# 7V4_2.net
KiCad netlist of a schematic drawn in Altium Designer
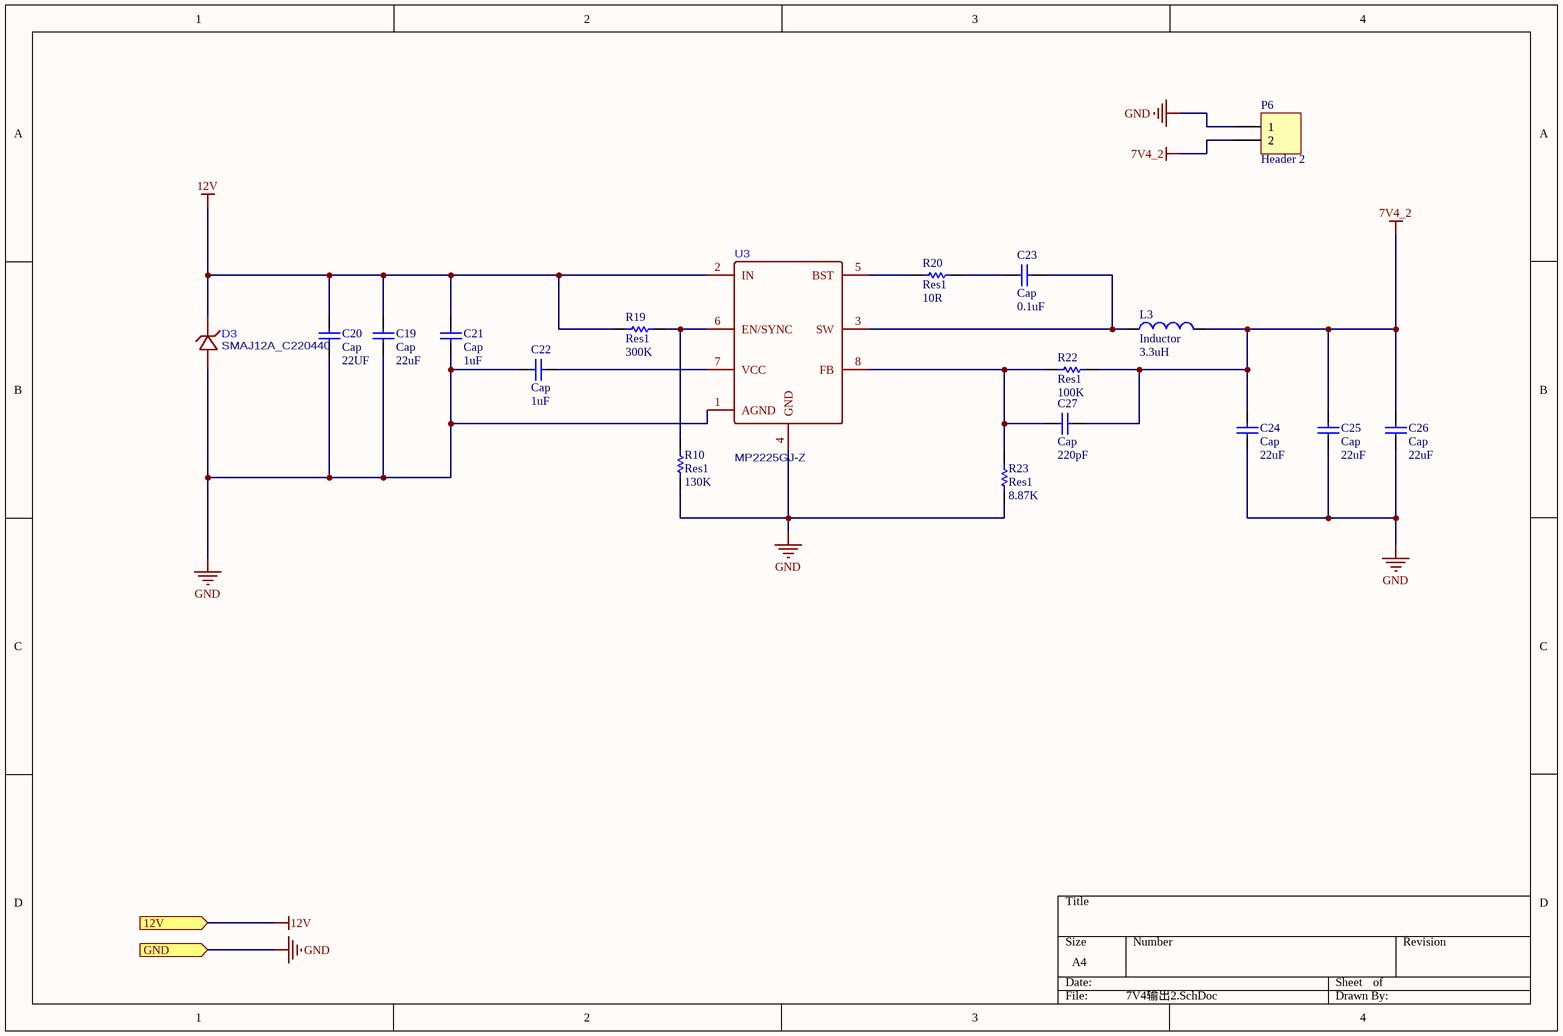
[diagram p0: 7V4输出2.SchDoc]

(export (version "E")
  (design (tool "Eeschema 10.0.6"))
  (components
    (comp (ref "C19")
      (value "Cap")
      (footprint "C1206")
      (description "Capacitor")
      (fields (field (name "ALTIUM_VALUE") "22uF") (field (name "PUBLISHER") "Altium Limited"))
      (libsource (lib "Miscellaneous Devices") (part "Cap"))
    )
    (comp (ref "C20")
      (value "Cap")
      (footprint "C1206")
      (description "Capacitor")
      (fields (field (name "ALTIUM_VALUE") "22UF") (field (name "PUBLISHER") "Altium Limited"))
      (libsource (lib "Miscellaneous Devices") (part "Cap"))
    )
    (comp (ref "C21")
      (value "Cap")
      (footprint "R0603")
      (description "Capacitor")
      (fields (field (name "ALTIUM_VALUE") "1uF") (field (name "PUBLISHER") "Altium Limited"))
      (libsource (lib "Miscellaneous Devices") (part "Cap"))
    )
    (comp (ref "C22")
      (value "Cap")
      (footprint "R0603")
      (description "Capacitor")
      (fields (field (name "ALTIUM_VALUE") "1uF") (field (name "PUBLISHER") "Altium Limited"))
      (libsource (lib "Miscellaneous Devices") (part "Cap"))
    )
    (comp (ref "C23")
      (value "Cap")
      (footprint "R0603")
      (description "Capacitor")
      (fields (field (name "ALTIUM_VALUE") "0.1uF") (field (name "PUBLISHER") "Altium Limited"))
      (libsource (lib "Miscellaneous Devices") (part "Cap"))
    )
    (comp (ref "C24")
      (value "Cap")
      (footprint "C0805")
      (description "Capacitor")
      (fields (field (name "ALTIUM_VALUE") "22uF") (field (name "PUBLISHER") "Altium Limited"))
      (libsource (lib "Miscellaneous Devices") (part "Cap"))
    )
    (comp (ref "C25")
      (value "Cap")
      (footprint "C0805")
      (description "Capacitor")
      (fields (field (name "ALTIUM_VALUE") "22uF") (field (name "PUBLISHER") "Altium Limited"))
      (libsource (lib "Miscellaneous Devices") (part "Cap"))
    )
    (comp (ref "C26")
      (value "Cap")
      (footprint "C0805")
      (description "Capacitor")
      (fields (field (name "ALTIUM_VALUE") "22uF") (field (name "PUBLISHER") "Altium Limited"))
      (libsource (lib "Miscellaneous Devices") (part "Cap"))
    )
    (comp (ref "C27")
      (value "Cap")
      (footprint "R0603")
      (description "Capacitor")
      (fields (field (name "ALTIUM_VALUE") "220pF") (field (name "PUBLISHER") "Altium Limited"))
      (libsource (lib "Miscellaneous Devices") (part "Cap"))
    )
    (comp (ref "D3")
      (value "SMAJ12A_C220440")
      (footprint "SMA_L4.4-W2.8-LS5.4-RD")
      (libsource (lib "SMAJ12A_C220440_2021-10-18") (part "SMAJ12A_C220440"))
    )
    (comp (ref "L3")
      (value "Inductor")
      (footprint "IND-SMD_L7.8-W7.0_MAPM0630F")
      (fields (field (name "ALTIUM_VALUE") "3.3uH") (field (name "PUBLISHER") "Altium Limited"))
      (libsource (lib "Miscellaneous Devices") (part "Inductor"))
    )
    (comp (ref "P6")
      (value "Header 2")
      (footprint "XH2.54-2A")
      (description "Header, 2-Pin")
      (fields (field (name "PUBLISHER") "Altium Limited"))
      (libsource (lib "Miscellaneous Connectors") (part "Header 2"))
    )
    (comp (ref "R10")
      (value "Res1")
      (footprint "R0603")
      (description "Resistor")
      (fields (field (name "ALTIUM_VALUE") "130K") (field (name "PUBLISHER") "Altium Limited"))
      (libsource (lib "Miscellaneous Devices") (part "Res1"))
    )
    (comp (ref "R19")
      (value "Res1")
      (footprint "R0603")
      (description "Resistor")
      (fields (field (name "ALTIUM_VALUE") "300K") (field (name "PUBLISHER") "Altium Limited"))
      (libsource (lib "Miscellaneous Devices") (part "Res1"))
    )
    (comp (ref "R20")
      (value "Res1")
      (footprint "R0603")
      (description "Resistor")
      (fields (field (name "ALTIUM_VALUE") "10R") (field (name "PUBLISHER") "Altium Limited"))
      (libsource (lib "Miscellaneous Devices") (part "Res1"))
    )
    (comp (ref "R22")
      (value "Res1")
      (footprint "R0603")
      (description "Resistor")
      (fields (field (name "ALTIUM_VALUE") "100K") (field (name "PUBLISHER") "Altium Limited"))
      (libsource (lib "Miscellaneous Devices") (part "Res1"))
    )
    (comp (ref "R23")
      (value "Res1")
      (footprint "R0603")
      (description "Resistor")
      (fields (field (name "ALTIUM_VALUE") "8.87K") (field (name "PUBLISHER") "Altium Limited"))
      (libsource (lib "Miscellaneous Devices") (part "Res1"))
    )
    (comp (ref "U3")
      (value "MP2225GJ-Z")
      (footprint "TSOT-23-8_L2.9-W1.6-P0.65-LS2.8-BR")
      (libsource (lib "MP2225GJ-Z_2021-10-18") (part "MP2225GJ-Z"))
    )
  )
  (nets
    (net (code "1") (name "7V4_2") (class "Default")
      (node (ref "C24") (pin "2") (pinfunction "2_2") (pintype "passive"))
      (node (ref "C25") (pin "2") (pinfunction "2_2") (pintype "passive"))
      (node (ref "C26") (pin "2") (pinfunction "2_2") (pintype "passive"))
      (node (ref "C27") (pin "2") (pinfunction "2_2") (pintype "passive"))
      (node (ref "L3") (pin "2") (pinfunction "2_2") (pintype "passive"))
      (node (ref "P6") (pin "2") (pinfunction "2_2") (pintype "passive"))
      (node (ref "R22") (pin "2") (pinfunction "2_2") (pintype "passive"))
    )
    (net (code "2") (name "12V") (class "Default")
      (node (ref "C19") (pin "2") (pinfunction "2_2") (pintype "passive"))
      (node (ref "C20") (pin "2") (pinfunction "2_2") (pintype "passive"))
      (node (ref "C21") (pin "2") (pinfunction "2_2") (pintype "passive"))
      (node (ref "D3") (pin "1") (pinfunction "1_1") (pintype "passive"))
      (node (ref "R19") (pin "1") (pinfunction "1_1") (pintype "passive"))
      (node (ref "U3") (pin "2") (pinfunction "IN_2") (pintype "passive"))
    )
    (net (code "3") (name "GND") (class "Default")
      (node (ref "C19") (pin "1") (pinfunction "1_1") (pintype "passive"))
      (node (ref "C20") (pin "1") (pinfunction "1_1") (pintype "passive"))
      (node (ref "C21") (pin "1") (pinfunction "1_1") (pintype "passive"))
      (node (ref "C22") (pin "1") (pinfunction "1_1") (pintype "passive"))
      (node (ref "C24") (pin "1") (pinfunction "1_1") (pintype "passive"))
      (node (ref "C25") (pin "1") (pinfunction "1_1") (pintype "passive"))
      (node (ref "C26") (pin "1") (pinfunction "1_1") (pintype "passive"))
      (node (ref "D3") (pin "2") (pinfunction "2_2") (pintype "passive"))
      (node (ref "P6") (pin "1") (pinfunction "1_1") (pintype "passive"))
      (node (ref "R10") (pin "1") (pinfunction "1_1") (pintype "passive"))
      (node (ref "R23") (pin "1") (pinfunction "1_1") (pintype "passive"))
      (node (ref "U3") (pin "1") (pinfunction "AGND_1") (pintype "passive"))
      (node (ref "U3") (pin "4") (pinfunction "GND_4") (pintype "passive"))
    )
    (net (code "4") (name "Net-(C23-Pad1)") (class "Default")
      (node (ref "C23") (pin "1") (pinfunction "1_1") (pintype "passive"))
      (node (ref "R20") (pin "2") (pinfunction "2_2") (pintype "passive"))
    )
    (net (code "5") (name "Net-(U3-BST)") (class "Default")
      (node (ref "R20") (pin "1") (pinfunction "1_1") (pintype "passive"))
      (node (ref "U3") (pin "5") (pinfunction "BST_5") (pintype "passive"))
    )
    (net (code "6") (name "Net-(U3-EN{slash}SYNC)") (class "Default")
      (node (ref "R10") (pin "2") (pinfunction "2_2") (pintype "passive"))
      (node (ref "R19") (pin "2") (pinfunction "2_2") (pintype "passive"))
      (node (ref "U3") (pin "6") (pinfunction "EN/SYNC_6") (pintype "passive"))
    )
    (net (code "7") (name "Net-(U3-FB)") (class "Default")
      (node (ref "C27") (pin "1") (pinfunction "1_1") (pintype "passive"))
      (node (ref "R22") (pin "1") (pinfunction "1_1") (pintype "passive"))
      (node (ref "R23") (pin "2") (pinfunction "2_2") (pintype "passive"))
      (node (ref "U3") (pin "8") (pinfunction "FB_8") (pintype "passive"))
    )
    (net (code "8") (name "Net-(U3-SW)") (class "Default")
      (node (ref "C23") (pin "2") (pinfunction "2_2") (pintype "passive"))
      (node (ref "L3") (pin "1") (pinfunction "1_1") (pintype "passive"))
      (node (ref "U3") (pin "3") (pinfunction "SW_3") (pintype "passive"))
    )
    (net (code "9") (name "Net-(U3-VCC)") (class "Default")
      (node (ref "C22") (pin "2") (pinfunction "2_2") (pintype "passive"))
      (node (ref "U3") (pin "7") (pinfunction "VCC_7") (pintype "passive"))
    )
  )
)
